# Oscillator_12MHz.net
KiCad netlist of a schematic drawn in Altium Designer
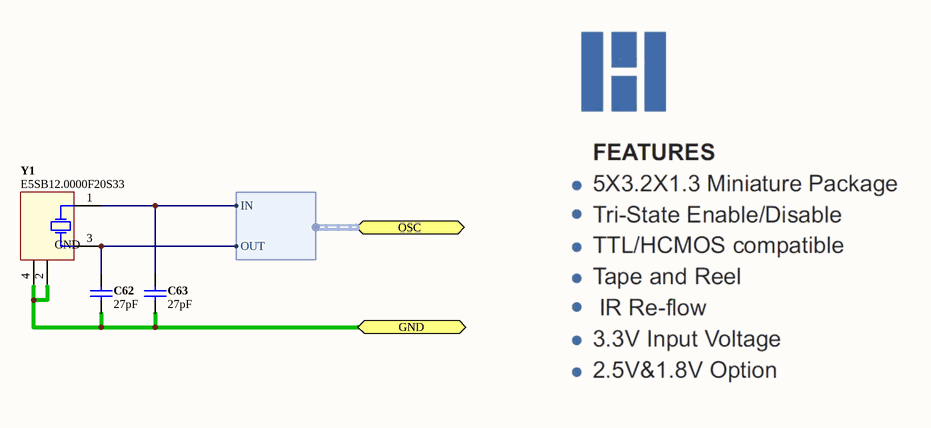
[diagram p0: Oscillator_12MHz.SchDoc]

(export (version "E")
  (design (tool "Eeschema 10.0.6"))
  (components
    (comp (ref "C62")
      (value "27pF")
      (footprint "CAPC0402(1005)60_N")
      (description "CAP 27pF 50V ±5% 0402 (1005 Metric) Thickness 0.6mm SMD")
      (fields (field (name "TOLERANCE") "±5%") (field (name "Comment") "CAP 27pF 50V 0402(1005)"))
      (libsource (lib "Altium Content Vault") (part "CMP-1034-00963-1"))
    )
    (comp (ref "C63")
      (value "27pF")
      (footprint "CAPC0402(1005)60_N")
      (description "CAP 27pF 50V ±5% 0402 (1005 Metric) Thickness 0.6mm SMD")
      (fields (field (name "TOLERANCE") "±5%") (field (name "Comment") "CAP 27pF 50V 0402(1005)"))
      (libsource (lib "Altium Content Vault") (part "CMP-1034-00963-1"))
    )
    (comp (ref "Y1")
      (value "E5SB12.0000F20S33")
      (footprint "HOSC-L500HW320H105-4")
      (description "Crystal, SMD, 12MHz, 10.0pF")
      (libsource (lib "Altium Content Vault") (part "CMP-5195-00000-1"))
    )
  )
  (nets
    (net (code "2") (name "/GND") (class "Default")
      (node (ref "C62") (pin "2") (pinfunction "2_2") (pintype "passive"))
      (node (ref "C63") (pin "2") (pinfunction "2_2") (pintype "passive"))
      (node (ref "Y1") (pin "2") (pinfunction "GND_2") (pintype "power_in"))
      (node (ref "Y1") (pin "4") (pinfunction "GND_4") (pintype "power_in"))
    )
    (net (code "4") (name "Net-(Y1-X1)") (class "Default")
      (node (ref "C63") (pin "1") (pinfunction "1_1") (pintype "passive"))
      (node (ref "Y1") (pin "1") (pinfunction "X1_1") (pintype "passive"))
    )
    (net (code "5") (name "Net-(Y1-X2)") (class "Default")
      (node (ref "C62") (pin "1") (pinfunction "1_1") (pintype "passive"))
      (node (ref "Y1") (pin "3") (pinfunction "X2_3") (pintype "passive"))
    )
  )
)
